# POWER.net
KiCad netlist of a schematic drawn in Altium Designer
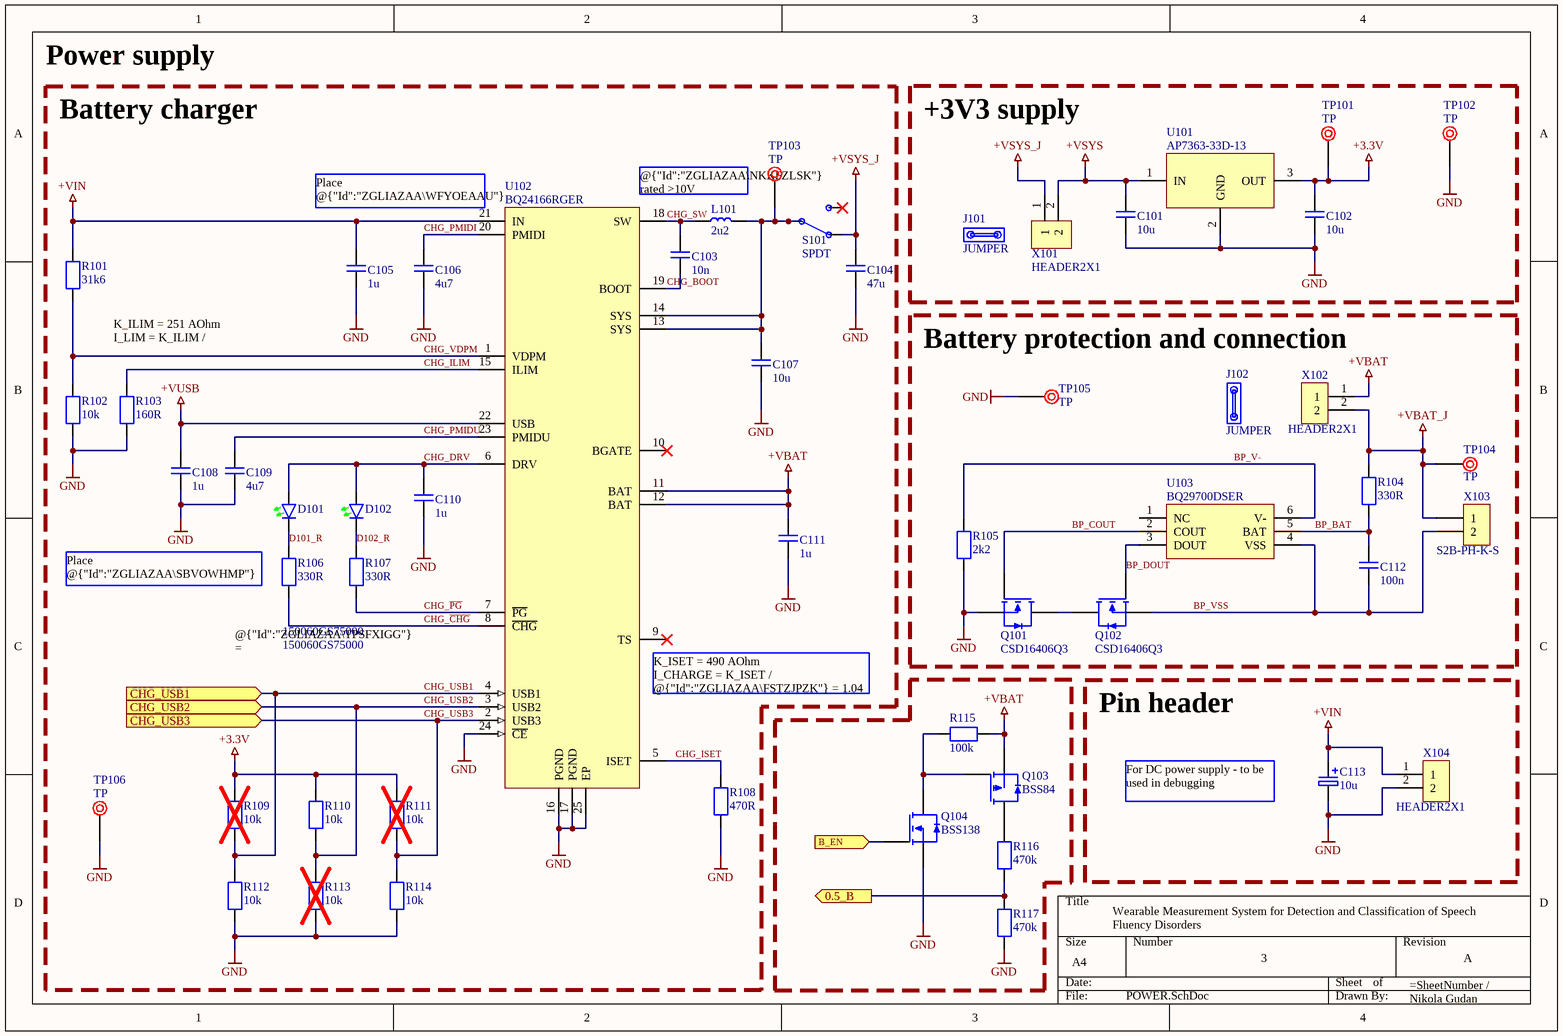
[diagram p0: POWER.SchDoc]

(export (version "E")
  (design (tool "Eeschema 10.0.6"))
  (components
    (comp (ref "C101")
      (value "10u")
      (footprint "CAPC0603")
      (description "Ceramic capacitor, VAL?,  VOL?, DIEL?")
      (fields (field (name "MFR") "?") (field (name "CHECKED") "Yes"))
      (libsource (lib "NG_Passive") (part "CAPC0603"))
    )
    (comp (ref "C102")
      (value "10u")
      (footprint "CAPC0603")
      (description "Ceramic capacitor, VAL?,  VOL?, DIEL?")
      (fields (field (name "MFR") "?") (field (name "CHECKED") "Yes"))
      (libsource (lib "NG_Passive") (part "CAPC0603"))
    )
    (comp (ref "C103")
      (value "10n")
      (footprint "CAPC0603")
      (description "Ceramic capacitor, VAL?,  VOL?, DIEL?")
      (fields (field (name "MFR") "?") (field (name "CHECKED") "Yes"))
      (libsource (lib "NG_Passive") (part "CAPC0603"))
    )
    (comp (ref "C104")
      (value "47u")
      (footprint "CAPC0805")
      (description "Ceramic capacitor, VAL?,  VOL?, DIEL?")
      (fields (field (name "MFR") "?") (field (name "CHECKED") "Yes"))
      (libsource (lib "NG_Passive") (part "CAPC0805"))
    )
    (comp (ref "C105")
      (value "1u")
      (footprint "CAPC0603")
      (description "Ceramic capacitor, VAL?,  VOL?, DIEL?")
      (fields (field (name "MFR") "?") (field (name "CHECKED") "Yes"))
      (libsource (lib "NG_Passive") (part "CAPC0603"))
    )
    (comp (ref "C106")
      (value "4u7")
      (footprint "CAPC0603")
      (description "Ceramic capacitor, VAL?,  VOL?, DIEL?")
      (fields (field (name "MFR") "?") (field (name "CHECKED") "Yes"))
      (libsource (lib "NG_Passive") (part "CAPC0603"))
    )
    (comp (ref "C107")
      (value "10u")
      (footprint "CAPC0603")
      (description "Ceramic capacitor, VAL?,  VOL?, DIEL?")
      (fields (field (name "MFR") "?") (field (name "CHECKED") "Yes"))
      (libsource (lib "NG_Passive") (part "CAPC0603"))
    )
    (comp (ref "C108")
      (value "1u")
      (footprint "CAPC0603")
      (description "Ceramic capacitor, VAL?,  VOL?, DIEL?")
      (fields (field (name "MFR") "?") (field (name "CHECKED") "Yes"))
      (libsource (lib "NG_Passive") (part "CAPC0603"))
    )
    (comp (ref "C109")
      (value "4u7")
      (footprint "CAPC0603")
      (description "Ceramic capacitor, VAL?,  VOL?, DIEL?")
      (fields (field (name "MFR") "?") (field (name "CHECKED") "Yes"))
      (libsource (lib "NG_Passive") (part "CAPC0603"))
    )
    (comp (ref "C110")
      (value "1u")
      (footprint "CAPC0603")
      (description "Ceramic capacitor, VAL?,  VOL?, DIEL?")
      (fields (field (name "MFR") "?") (field (name "CHECKED") "Yes"))
      (libsource (lib "NG_Passive") (part "CAPC0603"))
    )
    (comp (ref "C111")
      (value "1u")
      (footprint "CAPC0603")
      (description "Ceramic capacitor, VAL?,  VOL?, DIEL?")
      (fields (field (name "MFR") "?") (field (name "CHECKED") "Yes"))
      (libsource (lib "NG_Passive") (part "CAPC0603"))
    )
    (comp (ref "C112")
      (value "100n")
      (footprint "CAPC0603")
      (description "Ceramic capacitor, VAL?,  VOL?, DIEL?")
      (fields (field (name "MFR") "?") (field (name "CHECKED") "Yes"))
      (libsource (lib "NG_Passive") (part "CAPC0603"))
    )
    (comp (ref "C113")
      (value "10u")
      (footprint "CAPCP1206")
      (description "Tantalum capacitor, 10uF,  10V, 3.8Ohm")
      (fields
        (field (name "MFR") "KEMET")
        (field (name "LCSC PART NUMBER") "C1508940")
        (field (name "CHECKED") "Yes")
      )
      (libsource (lib "NG_Passive") (part "CAPCP1206-10u-10"))
    )
    (comp (ref "D101")
      (value "150060GS75000")
      (footprint "LED0603")
      (description "LED Green, 2.1V, 20mA")
      (fields
        (field (name "MFR") "Würth Elektronik")
        (field (name "LCSC PART NUMBER") "C913102")
        (field (name "CHECKED") "Yes")
      )
      (libsource (lib "NG_Active") (part "LTST-C194KGKT"))
    )
    (comp (ref "D102")
      (value "150060GS75000")
      (footprint "LED0603")
      (description "LED Green, 2.1V, 20mA")
      (fields
        (field (name "MFR") "Würth Elektronik")
        (field (name "LCSC PART NUMBER") "C913102")
        (field (name "CHECKED") "Yes")
      )
      (libsource (lib "NG_Active") (part "LTST-C194KGKT"))
    )
    (comp (ref "J101")
      (value "JUMPER")
      (description "Open Top 3A 2.54mm P=2.54mm Shunts & Jumpers ROHS")
      (fields
        (field (name "MFR") "Kycon, Inc.")
        (field (name "LCSC PART NUMBER") "C5305")
        (field (name "CHECKED") "Yes")
      )
      (libsource (lib "NG_Mechanical") (part "JUMPER"))
    )
    (comp (ref "J102")
      (value "JUMPER")
      (description "Open Top 3A 2.54mm P=2.54mm Shunts & Jumpers ROHS")
      (fields
        (field (name "MFR") "Kycon, Inc.")
        (field (name "LCSC PART NUMBER") "C5305")
        (field (name "CHECKED") "Yes")
      )
      (libsource (lib "NG_Mechanical") (part "JUMPER"))
    )
    (comp (ref "L101")
      (value "2u2")
      (footprint "INDM4145X18")
      (description "Inductor 2.2uH, 4A, ±20%, 61mOhm")
      (fields
        (field (name "MFR") "Bourns Inc.")
        (field (name "LCSC PART NUMBER") "C2847469")
        (field (name "CHECKED") "Yes")
      )
      (libsource (lib "NG_Passive") (part "INDM4145-2u2-20"))
    )
    (comp (ref "Q101")
      (value "CSD16406Q3")
      (footprint "TRANS_CSD16406Q3")
      (description "MOSFET N-CH 25V 60A 8VSON")
      (fields
        (field (name "MFR") "Texas Instruments")
        (field (name "LCSC PART NUMBER") "C2861720")
        (field (name "CHECKED") "Yes")
      )
      (libsource (lib "NG_Active") (part "CSD16406Q3"))
    )
    (comp (ref "Q102")
      (value "CSD16406Q3")
      (footprint "TRANS_CSD16406Q3")
      (description "MOSFET N-CH 25V 60A 8VSON")
      (fields
        (field (name "MFR") "Texas Instruments")
        (field (name "LCSC PART NUMBER") "C2861720")
        (field (name "CHECKED") "Yes")
      )
      (libsource (lib "NG_Active") (part "CSD16406Q3"))
    )
    (comp (ref "Q103")
      (value "BSS84")
      (footprint "SOT190P240X290-3")
      (description "MOSFET P-CH 50V 130mA SOT23-3")
      (fields
        (field (name "MFR") "onsemi")
        (field (name "LCSC PART NUMBER") "C266796")
        (field (name "CHECKED") "Yes")
      )
      (libsource (lib "NG_Active") (part "BSS84"))
    )
    (comp (ref "Q104")
      (value "BSS138")
      (footprint "SOT190P240X290-3")
      (description "MOSFET N-CH 50V 220mA SOT23-3")
      (fields
        (field (name "MFR") "onsemi")
        (field (name "LCSC PART NUMBER") "C52895")
        (field (name "CHECKED") "Yes")
      )
      (libsource (lib "NG_Active") (part "BSS138"))
    )
    (comp (ref "R101")
      (value "31k6")
      (footprint "RESC0603")
      (description "Thick film resistor, VAL?, POW?")
      (fields (field (name "MFR") "?") (field (name "CHECKED") "Yes"))
      (libsource (lib "NG_Passive") (part "RES0603"))
    )
    (comp (ref "R102")
      (value "10k")
      (footprint "RESC0603")
      (description "Thick film resistor, VAL?, POW?")
      (fields (field (name "MFR") "?") (field (name "CHECKED") "Yes"))
      (libsource (lib "NG_Passive") (part "RES0603"))
    )
    (comp (ref "R103")
      (value "160R")
      (footprint "RESC0603")
      (description "Thick film resistor, VAL?, POW?")
      (fields (field (name "MFR") "?") (field (name "CHECKED") "Yes"))
      (libsource (lib "NG_Passive") (part "RES0603"))
    )
    (comp (ref "R104")
      (value "330R")
      (footprint "RESC0603")
      (description "Thick film resistor, VAL?, POW?")
      (fields (field (name "MFR") "?") (field (name "CHECKED") "Yes"))
      (libsource (lib "NG_Passive") (part "RES0603"))
    )
    (comp (ref "R105")
      (value "2k2")
      (footprint "RESC0603")
      (description "Thick film resistor, VAL?, POW?")
      (fields (field (name "MFR") "?") (field (name "CHECKED") "Yes"))
      (libsource (lib "NG_Passive") (part "RES0603"))
    )
    (comp (ref "R106")
      (value "330R")
      (footprint "RESC0603")
      (description "Thick film resistor, VAL?, POW?")
      (fields (field (name "MFR") "?") (field (name "CHECKED") "Yes"))
      (libsource (lib "NG_Passive") (part "RES0603"))
    )
    (comp (ref "R107")
      (value "330R")
      (footprint "RESC0603")
      (description "Thick film resistor, VAL?, POW?")
      (fields (field (name "MFR") "?") (field (name "CHECKED") "Yes"))
      (libsource (lib "NG_Passive") (part "RES0603"))
    )
    (comp (ref "R108")
      (value "470R")
      (footprint "RESC0603")
      (description "Thick film resistor, VAL?, POW?")
      (fields (field (name "MFR") "?") (field (name "CHECKED") "Yes"))
      (libsource (lib "NG_Passive") (part "RES0603"))
    )
    (comp (ref "R109")
      (value "10k")
      (footprint "RESC0603")
      (description "Thick film resistor, VAL?, POW?")
      (fields (field (name "MFR") "?") (field (name "CHECKED") "Yes"))
      (libsource (lib "NG_Passive") (part "RES0603"))
    )
    (comp (ref "R110")
      (value "10k")
      (footprint "RESC0603")
      (description "Thick film resistor, VAL?, POW?")
      (fields (field (name "MFR") "?") (field (name "CHECKED") "Yes"))
      (libsource (lib "NG_Passive") (part "RES0603"))
    )
    (comp (ref "R111")
      (value "10k")
      (footprint "RESC0603")
      (description "Thick film resistor, VAL?, POW?")
      (fields (field (name "MFR") "?") (field (name "CHECKED") "Yes"))
      (libsource (lib "NG_Passive") (part "RES0603"))
    )
    (comp (ref "R112")
      (value "10k")
      (footprint "RESC0603")
      (description "Thick film resistor, VAL?, POW?")
      (fields (field (name "MFR") "?") (field (name "CHECKED") "Yes"))
      (libsource (lib "NG_Passive") (part "RES0603"))
    )
    (comp (ref "R113")
      (value "10k")
      (footprint "RESC0603")
      (description "Thick film resistor, VAL?, POW?")
      (fields (field (name "MFR") "?") (field (name "CHECKED") "Yes"))
      (libsource (lib "NG_Passive") (part "RES0603"))
    )
    (comp (ref "R114")
      (value "10k")
      (footprint "RESC0603")
      (description "Thick film resistor, VAL?, POW?")
      (fields (field (name "MFR") "?") (field (name "CHECKED") "Yes"))
      (libsource (lib "NG_Passive") (part "RES0603"))
    )
    (comp (ref "R115")
      (value "100k")
      (footprint "RESC0603")
      (description "Thick film resistor, VAL?, POW?")
      (fields (field (name "MFR") "?") (field (name "CHECKED") "Yes"))
      (libsource (lib "NG_Passive") (part "RES0603"))
    )
    (comp (ref "R116")
      (value "470k")
      (footprint "RESC0603")
      (description "Thick film resistor, VAL?, POW?")
      (fields (field (name "MFR") "?") (field (name "CHECKED") "Yes"))
      (libsource (lib "NG_Passive") (part "RES0603"))
    )
    (comp (ref "R117")
      (value "470k")
      (footprint "RESC0603")
      (description "Thick film resistor, VAL?, POW?")
      (fields (field (name "MFR") "?") (field (name "CHECKED") "Yes"))
      (libsource (lib "NG_Passive") (part "RES0603"))
    )
    (comp (ref "S101")
      (value "SPDT")
      (footprint "SW_EG1247")
      (description "Slide switch, SPDT, 30V, 200mA")
      (fields (field (name "MFR") "E-Switch") (field (name "CHECKED") "Yes"))
      (libsource (lib "NG_Mechanical") (part "SLIDE SW SPDT"))
    )
    (comp (ref "TP101")
      (value "TP")
      (footprint "TESTPOINT")
      (description "Testpoint")
      (fields
        (field (name "MFR") "Keystone")
        (field (name "LCSC PART NUMBER") "C238122")
        (field (name "CHECKED") "Yes")
      )
      (libsource (lib "NG_Mechanical") (part "TESTPOINT"))
    )
    (comp (ref "TP102")
      (value "TP")
      (footprint "TESTPOINT")
      (description "Testpoint")
      (fields
        (field (name "MFR") "Keystone")
        (field (name "LCSC PART NUMBER") "C238122")
        (field (name "CHECKED") "Yes")
      )
      (libsource (lib "NG_Mechanical") (part "TESTPOINT"))
    )
    (comp (ref "TP103")
      (value "TP")
      (footprint "TESTPOINT")
      (description "Testpoint")
      (fields
        (field (name "MFR") "Keystone")
        (field (name "LCSC PART NUMBER") "C238122")
        (field (name "CHECKED") "Yes")
      )
      (libsource (lib "NG_Mechanical") (part "TESTPOINT"))
    )
    (comp (ref "TP104")
      (value "TP")
      (footprint "TESTPOINT")
      (description "Testpoint")
      (fields
        (field (name "MFR") "Keystone")
        (field (name "LCSC PART NUMBER") "C238122")
        (field (name "CHECKED") "Yes")
      )
      (libsource (lib "NG_Mechanical") (part "TESTPOINT"))
    )
    (comp (ref "TP105")
      (value "TP")
      (footprint "TESTPOINT")
      (description "Testpoint")
      (fields
        (field (name "MFR") "Keystone")
        (field (name "LCSC PART NUMBER") "C238122")
        (field (name "CHECKED") "Yes")
      )
      (libsource (lib "NG_Mechanical") (part "TESTPOINT"))
    )
    (comp (ref "TP106")
      (value "TP")
      (footprint "TESTPOINT")
      (description "Testpoint")
      (fields
        (field (name "MFR") "Keystone")
        (field (name "LCSC PART NUMBER") "C238122")
        (field (name "CHECKED") "Yes")
      )
      (libsource (lib "NG_Mechanical") (part "TESTPOINT"))
    )
    (comp (ref "U101")
      (value "AP7363-33D-13")
      (footprint "TO457X991X229-3")
      (description "Linear LDO Voltage Regulator, 3.3V, 1.5A")
      (fields
        (field (name "MFR") "Diodes Incorporated")
        (field (name "LCSC PART NUMBER") "C108723")
        (field (name "CHECKED") "Yes")
      )
      (libsource (lib "NG_Analog") (part "IC REG LINEAR AP7363-33D-13"))
    )
    (comp (ref "U102")
      (value "BQ24166RGER")
      (footprint "QFN50P410X410X100-24EP")
      (description "IC Battery Charger, Li-Ion, 1 Cell, 3.7V, 2.5A")
      (fields
        (field (name "MFR") "Texas Instruments")
        (field (name "LCSC PART NUMBER") "C2758608")
        (field (name "CHECKED") "Yes")
      )
      (libsource (lib "NG_Analog") (part "IC BATT CHG LI-ION BQ24166"))
    )
    (comp (ref "U103")
      (value "BQ29700DSER")
      (footprint "WSON50P150X150X80-6")
      (description "Battery Protection IC Li-Ion 1Cell")
      (fields
        (field (name "MFR") "Texas Instruments")
        (field (name "LCSC PART NUMBER") "C183096")
        (field (name "CHECKED") "Yes")
      )
      (libsource (lib "NG_Analog") (part "IC BATT PROT BQ29700DSER"))
    )
    (comp (ref "X101")
      (value "HEADER2X1")
      (footprint "HDRV2W64P254_2X1_508X254X1150")
      (description "Pin Header 2x1, P2.54")
      (fields
        (field (name "MFR") "Adam Tech")
        (field (name "LCSC PART NUMBER") "C2883961")
        (field (name "CHECKED") "Yes")
      )
      (libsource (lib "NG_Mechanical") (part "HEADER2X1"))
    )
    (comp (ref "X102")
      (value "HEADER2X1")
      (footprint "HDRV2W64P254_2X1_508X254X1150")
      (description "Pin Header 2x1, P2.54")
      (fields
        (field (name "MFR") "Adam Tech")
        (field (name "LCSC PART NUMBER") "C2883961")
        (field (name "CHECKED") "Yes")
      )
      (libsource (lib "") (part "HEADER2X1_2"))
    )
    (comp (ref "X103")
      (value "S2B-PH-K-S")
      (footprint "JST_S2B-PH-K-S")
      (description "JST PH Connector 2POS R/A THT")
      (fields
        (field (name "MFR") "JST Sales America Inc.")
        (field (name "LCSC PART NUMBER") "C173752")
        (field (name "CHECKED") "Yes")
      )
      (libsource (lib "NG_Mechanical") (part "JST S2B-PH-K-S"))
    )
    (comp (ref "X104")
      (value "HEADER2X1")
      (footprint "HDRV2W64P254_2X1_508X254X1150")
      (description "Pin Header 2x1, P2.54")
      (fields
        (field (name "MFR") "Adam Tech")
        (field (name "LCSC PART NUMBER") "C2883961")
        (field (name "CHECKED") "Yes")
      )
      (libsource (lib "") (part "HEADER2X1_1"))
    )
  )
  (nets
    (net (code "1") (name "+3.3V") (class "Default")
      (node (ref "C102") (pin "2") (pinfunction "2_2") (pintype "passive"))
      (node (ref "R109") (pin "1") (pinfunction "1_1") (pintype "passive"))
      (node (ref "R110") (pin "1") (pinfunction "1_1") (pintype "passive"))
      (node (ref "R111") (pin "1") (pinfunction "1_1") (pintype "passive"))
      (node (ref "TP101") (pin "1") (pinfunction "1_1") (pintype "passive"))
      (node (ref "U101") (pin "3") (pinfunction "OUT_3") (pintype "power_in"))
    )
    (net (code "2") (name "+VBAT") (class "Default")
      (node (ref "C111") (pin "2") (pinfunction "2_2") (pintype "passive"))
      (node (ref "Q103") (pin "2") (pinfunction "S_2") (pintype "passive"))
      (node (ref "R115") (pin "1") (pinfunction "1_1") (pintype "passive"))
      (node (ref "U102") (pin "11") (pinfunction "BAT_11") (pintype "power_in"))
      (node (ref "U102") (pin "12") (pinfunction "BAT_12") (pintype "power_in"))
      (node (ref "X102") (pin "1") (pinfunction "1_1") (pintype "passive"))
    )
    (net (code "3") (name "+VBAT_J") (class "Default")
      (node (ref "R104") (pin "2") (pinfunction "2_2") (pintype "passive"))
      (node (ref "TP104") (pin "1") (pinfunction "1_1") (pintype "passive"))
      (node (ref "X102") (pin "2") (pinfunction "2_2") (pintype "passive"))
      (node (ref "X103") (pin "1") (pinfunction "1_1") (pintype "passive"))
    )
    (net (code "4") (name "+VIN") (class "Default")
      (node (ref "C105") (pin "2") (pinfunction "2_2") (pintype "passive"))
      (node (ref "C113") (pin "1") (pinfunction "1_1") (pintype "passive"))
      (node (ref "R101") (pin "2") (pinfunction "2_2") (pintype "passive"))
      (node (ref "U102") (pin "21") (pinfunction "IN_21") (pintype "power_in"))
      (node (ref "X104") (pin "1") (pinfunction "1_1") (pintype "passive"))
    )
    (net (code "5") (name "+VSYS") (class "Default")
      (node (ref "C101") (pin "2") (pinfunction "2_2") (pintype "passive"))
      (node (ref "U101") (pin "1") (pinfunction "IN_1") (pintype "power_in"))
      (node (ref "X101") (pin "2") (pinfunction "2_2") (pintype "passive"))
    )
    (net (code "6") (name "+VSYS_J") (class "Default")
      (node (ref "C104") (pin "2") (pinfunction "2_2") (pintype "passive"))
      (node (ref "S101") (pin "1") (pinfunction "1_1") (pintype "passive"))
      (node (ref "X101") (pin "1") (pinfunction "1_1") (pintype "passive"))
    )
    (net (code "7") (name "+VUSB") (class "Default")
      (node (ref "C108") (pin "2") (pinfunction "2_2") (pintype "passive"))
      (node (ref "U102") (pin "22") (pinfunction "USB_22") (pintype "power_in"))
    )
    (net (code "8") (name "/0.5_B") (class "Default")
      (node (ref "R116") (pin "2") (pinfunction "2_2") (pintype "passive"))
      (node (ref "R117") (pin "1") (pinfunction "1_1") (pintype "passive"))
    )
    (net (code "9") (name "/BP_BAT") (class "Default")
      (node (ref "C112") (pin "2") (pinfunction "2_2") (pintype "passive"))
      (node (ref "R104") (pin "1") (pinfunction "1_1") (pintype "passive"))
      (node (ref "U103") (pin "5") (pinfunction "BAT_5") (pintype "power_in"))
    )
    (net (code "10") (name "/BP_COUT") (class "Default")
      (node (ref "Q101") (pin "3") (pinfunction "G_3") (pintype "passive"))
      (node (ref "U103") (pin "2") (pinfunction "COUT_2") (pintype "passive"))
    )
    (net (code "11") (name "/BP_DOUT") (class "Default")
      (node (ref "Q102") (pin "3") (pinfunction "G_3") (pintype "passive"))
      (node (ref "U103") (pin "3") (pinfunction "DOUT_3") (pintype "passive"))
    )
    (net (code "12") (name "/BP_V-") (class "Default")
      (node (ref "R105") (pin "2") (pinfunction "2_2") (pintype "passive"))
      (node (ref "U103") (pin "6") (pinfunction "V-_6") (pintype "power_in"))
    )
    (net (code "13") (name "/BP_VSS") (class "Default")
      (node (ref "C112") (pin "1") (pinfunction "1_1") (pintype "passive"))
      (node (ref "Q102") (pin "1") (pinfunction "S_1") (pintype "passive"))
      (node (ref "U103") (pin "4") (pinfunction "VSS_4") (pintype "power_in"))
      (node (ref "X103") (pin "2") (pinfunction "2_2") (pintype "passive"))
    )
    (net (code "14") (name "/B_EN") (class "Default")
      (node (ref "Q104") (pin "1") (pinfunction "G_1") (pintype "passive"))
    )
    (net (code "15") (name "/CHG_BOOT") (class "Default")
      (node (ref "C103") (pin "1") (pinfunction "1_1") (pintype "passive"))
      (node (ref "U102") (pin "19") (pinfunction "BOOT_19") (pintype "passive"))
    )
    (net (code "16") (name "/CHG_DRV") (class "Default")
      (node (ref "C110") (pin "2") (pinfunction "2_2") (pintype "passive"))
      (node (ref "D101") (pin "2") (pinfunction "2_2") (pintype "passive"))
      (node (ref "D102") (pin "2") (pinfunction "2_2") (pintype "passive"))
      (node (ref "U102") (pin "6") (pinfunction "DRV_6") (pintype "passive"))
    )
    (net (code "17") (name "/CHG_ILIM") (class "Default")
      (node (ref "R103") (pin "1") (pinfunction "1_1") (pintype "passive"))
      (node (ref "U102") (pin "15") (pinfunction "ILIM_15") (pintype "power_in"))
    )
    (net (code "18") (name "/CHG_ISET") (class "Default")
      (node (ref "R108") (pin "2") (pinfunction "2_2") (pintype "passive"))
      (node (ref "U102") (pin "5") (pinfunction "ISET_5") (pintype "passive"))
    )
    (net (code "19") (name "/CHG_PMIDI") (class "Default")
      (node (ref "C106") (pin "2") (pinfunction "2_2") (pintype "passive"))
      (node (ref "U102") (pin "20") (pinfunction "PMIDI_20") (pintype "power_in"))
    )
    (net (code "20") (name "/CHG_PMIDU") (class "Default")
      (node (ref "C109") (pin "2") (pinfunction "2_2") (pintype "passive"))
      (node (ref "U102") (pin "23") (pinfunction "PMIDU_23") (pintype "power_in"))
    )
    (net (code "21") (name "/CHG_SW") (class "Default")
      (node (ref "C103") (pin "2") (pinfunction "2_2") (pintype "passive"))
      (node (ref "L101") (pin "1") (pinfunction "1_1") (pintype "passive"))
      (node (ref "U102") (pin "18") (pinfunction "SW_18") (pintype "power_in"))
    )
    (net (code "22") (name "/CHG_USB1") (class "Default")
      (node (ref "R109") (pin "2") (pinfunction "2_2") (pintype "passive"))
      (node (ref "R112") (pin "1") (pinfunction "1_1") (pintype "passive"))
      (node (ref "U102") (pin "4") (pinfunction "USB1_4") (pintype "input"))
    )
    (net (code "23") (name "/CHG_USB2") (class "Default")
      (node (ref "R110") (pin "2") (pinfunction "2_2") (pintype "passive"))
      (node (ref "R113") (pin "1") (pinfunction "1_1") (pintype "passive"))
      (node (ref "U102") (pin "3") (pinfunction "USB2_3") (pintype "input"))
    )
    (net (code "24") (name "/CHG_USB3") (class "Default")
      (node (ref "R111") (pin "2") (pinfunction "2_2") (pintype "passive"))
      (node (ref "R114") (pin "1") (pinfunction "1_1") (pintype "passive"))
      (node (ref "U102") (pin "2") (pinfunction "USB3_2") (pintype "input"))
    )
    (net (code "25") (name "/CHG_VDPM") (class "Default")
      (node (ref "R101") (pin "1") (pinfunction "1_1") (pintype "passive"))
      (node (ref "R102") (pin "1") (pinfunction "1_1") (pintype "passive"))
      (node (ref "U102") (pin "1") (pinfunction "VDPM_1") (pintype "power_in"))
    )
    (net (code "26") (name "/CHG_~{CHG}") (class "Default")
      (node (ref "R106") (pin "1") (pinfunction "1_1") (pintype "passive"))
      (node (ref "U102") (pin "8") (pinfunction "~{CHG}_8") (pintype "open_collector"))
    )
    (net (code "27") (name "/CHG_~{PG}") (class "Default")
      (node (ref "R107") (pin "1") (pinfunction "1_1") (pintype "passive"))
      (node (ref "U102") (pin "7") (pinfunction "~{PG}_7") (pintype "open_collector"))
    )
    (net (code "28") (name "/D101_R") (class "Default")
      (node (ref "D101") (pin "1") (pinfunction "1_1") (pintype "passive"))
      (node (ref "R106") (pin "2") (pinfunction "2_2") (pintype "passive"))
    )
    (net (code "29") (name "/D102_R") (class "Default")
      (node (ref "D102") (pin "1") (pinfunction "1_1") (pintype "passive"))
      (node (ref "R107") (pin "2") (pinfunction "2_2") (pintype "passive"))
    )
    (net (code "30") (name "GND") (class "Default")
      (node (ref "C101") (pin "1") (pinfunction "1_1") (pintype "passive"))
      (node (ref "C102") (pin "1") (pinfunction "1_1") (pintype "passive"))
      (node (ref "C104") (pin "1") (pinfunction "1_1") (pintype "passive"))
      (node (ref "C105") (pin "1") (pinfunction "1_1") (pintype "passive"))
      (node (ref "C106") (pin "1") (pinfunction "1_1") (pintype "passive"))
      (node (ref "C107") (pin "1") (pinfunction "1_1") (pintype "passive"))
      (node (ref "C108") (pin "1") (pinfunction "1_1") (pintype "passive"))
      (node (ref "C109") (pin "1") (pinfunction "1_1") (pintype "passive"))
      (node (ref "C110") (pin "1") (pinfunction "1_1") (pintype "passive"))
      (node (ref "C111") (pin "1") (pinfunction "1_1") (pintype "passive"))
      (node (ref "C113") (pin "2") (pinfunction "2_2") (pintype "passive"))
      (node (ref "Q101") (pin "1") (pinfunction "S_1") (pintype "passive"))
      (node (ref "Q104") (pin "2") (pinfunction "S_2") (pintype "passive"))
      (node (ref "R102") (pin "2") (pinfunction "2_2") (pintype "passive"))
      (node (ref "R103") (pin "2") (pinfunction "2_2") (pintype "passive"))
      (node (ref "R105") (pin "1") (pinfunction "1_1") (pintype "passive"))
      (node (ref "R108") (pin "1") (pinfunction "1_1") (pintype "passive"))
      (node (ref "R112") (pin "2") (pinfunction "2_2") (pintype "passive"))
      (node (ref "R113") (pin "2") (pinfunction "2_2") (pintype "passive"))
      (node (ref "R114") (pin "2") (pinfunction "2_2") (pintype "passive"))
      (node (ref "R117") (pin "2") (pinfunction "2_2") (pintype "passive"))
      (node (ref "TP102") (pin "1") (pinfunction "1_1") (pintype "passive"))
      (node (ref "TP105") (pin "1") (pinfunction "1_1") (pintype "passive"))
      (node (ref "TP106") (pin "1") (pinfunction "1_1") (pintype "passive"))
      (node (ref "U101") (pin "2") (pinfunction "GND_2") (pintype "power_in"))
      (node (ref "U102") (pin "16") (pinfunction "PGND_16") (pintype "passive"))
      (node (ref "U102") (pin "17") (pinfunction "PGND_17") (pintype "passive"))
      (node (ref "U102") (pin "24") (pinfunction "~{CE}_24") (pintype "input"))
      (node (ref "U102") (pin "25") (pinfunction "EP_25") (pintype "passive"))
      (node (ref "X104") (pin "2") (pinfunction "2_2") (pintype "passive"))
    )
    (net (code "31") (name "Net-(C107-Pad2)") (class "Default")
      (node (ref "C107") (pin "2") (pinfunction "2_2") (pintype "passive"))
      (node (ref "L101") (pin "2") (pinfunction "2_2") (pintype "passive"))
      (node (ref "S101") (pin "2") (pinfunction "2_2") (pintype "passive"))
      (node (ref "TP103") (pin "1") (pinfunction "1_1") (pintype "passive"))
      (node (ref "U102") (pin "13") (pinfunction "SYS_13") (pintype "passive"))
      (node (ref "U102") (pin "14") (pinfunction "SYS_14") (pintype "passive"))
    )
    (net (code "32") (name "Net-(Q101-D)") (class "Default")
      (node (ref "Q101") (pin "2") (pinfunction "D_2") (pintype "passive"))
      (node (ref "Q102") (pin "2") (pinfunction "D_2") (pintype "passive"))
    )
    (net (code "33") (name "Net-(Q103-D)") (class "Default")
      (node (ref "Q103") (pin "3") (pinfunction "D_3") (pintype "passive"))
      (node (ref "R116") (pin "1") (pinfunction "1_1") (pintype "passive"))
    )
    (net (code "34") (name "Net-(Q103-G)") (class "Default")
      (node (ref "Q103") (pin "1") (pinfunction "G_1") (pintype "passive"))
      (node (ref "Q104") (pin "3") (pinfunction "D_3") (pintype "passive"))
      (node (ref "R115") (pin "2") (pinfunction "2_2") (pintype "passive"))
    )
    (net (code "35") (name "unconnected-(S101-Pad3)") (class "Default")
      (node (ref "S101") (pin "3") (pinfunction "3_3") (pintype "passive+no_connect"))
    )
    (net (code "36") (name "unconnected-(U102-BGATE-Pad10)") (class "Default")
      (node (ref "U102") (pin "10") (pinfunction "BGATE_10") (pintype "tri_state+no_connect"))
    )
    (net (code "37") (name "unconnected-(U102-TS-Pad9)") (class "Default")
      (node (ref "U102") (pin "9") (pinfunction "TS_9") (pintype "passive+no_connect"))
    )
    (net (code "38") (name "unconnected-(U103-NC-Pad1)") (class "Default")
      (node (ref "U103") (pin "1") (pinfunction "NC_1") (pintype "passive"))
    )
  )
)
